# 20_WiFi_BT.net
KiCad netlist of a schematic drawn in Altium Designer
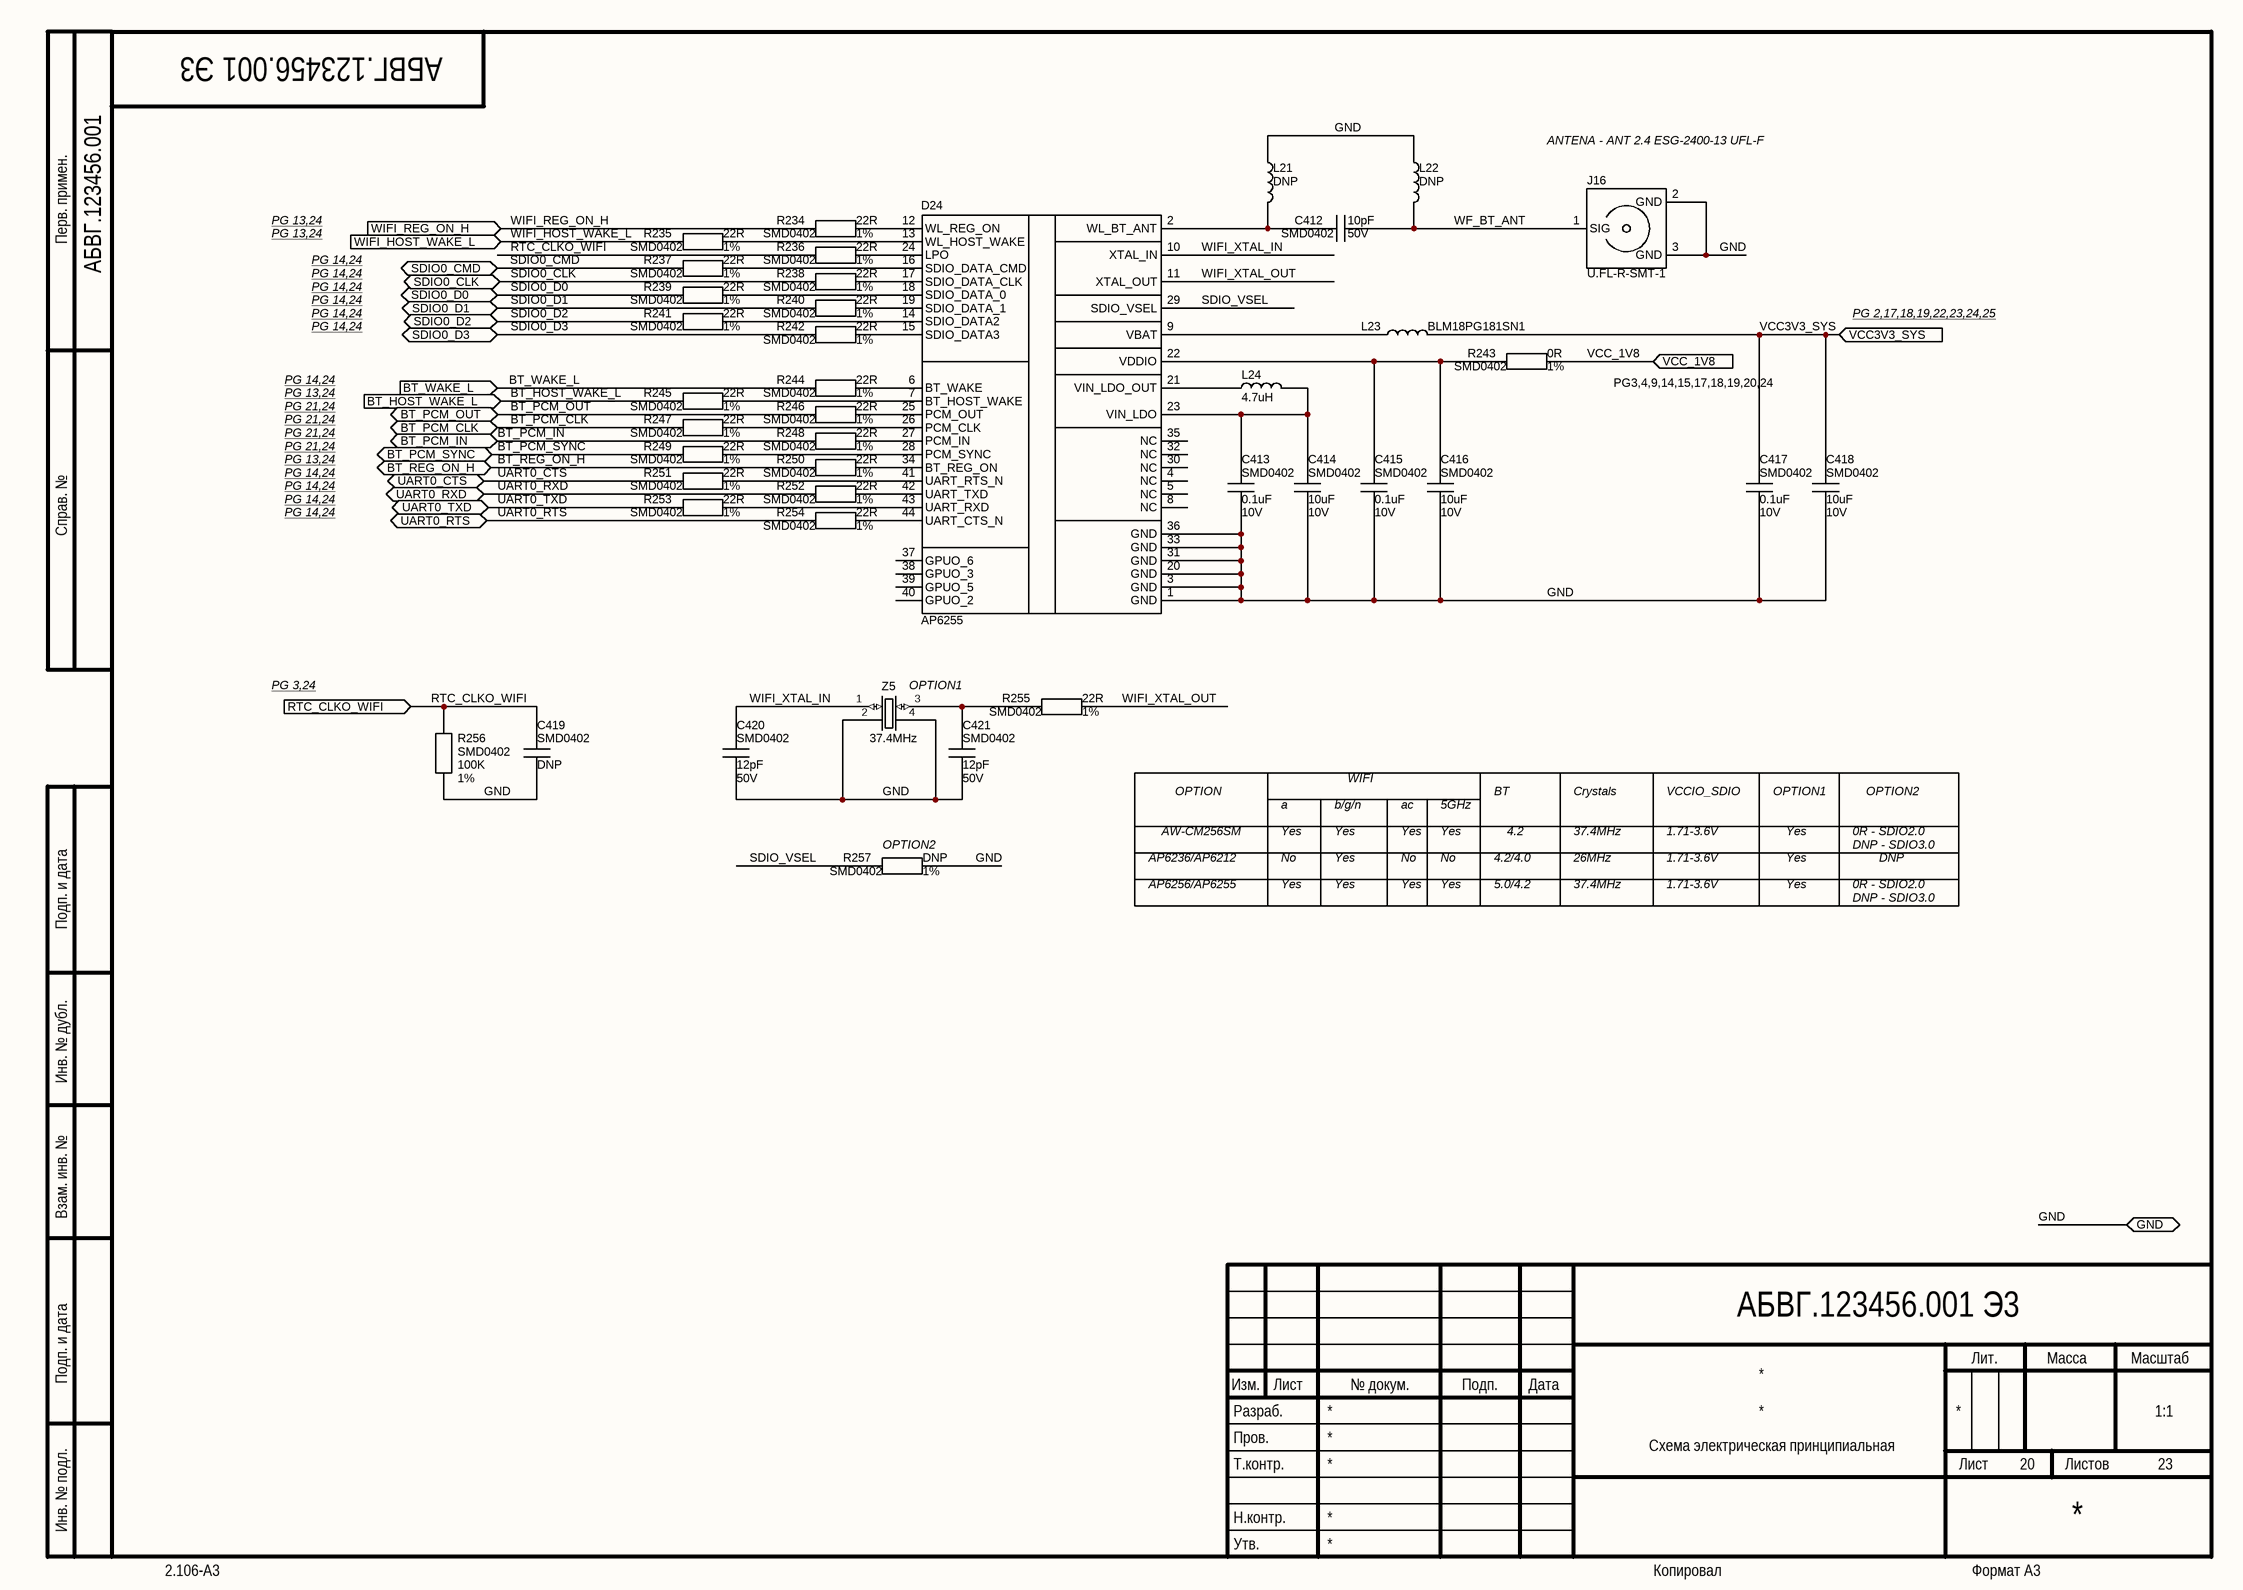
[diagram p0: 20 WiFi_BT.SchDoc]

(export (version "E")
  (design (tool "Eeschema 10.0.6"))
  (components
    (comp (ref "C412")
      (value "10pF")
      (footprint "Didur_PcbLib_1:CAP_SMD_0402")
      (fields
        (field (name "PACKAGE") "SMD0402")
        (field (name "PARTNUMBER") "CC0402CRNPO9BN100")
        (field (name "VOLTAGE") "50V")
      )
      (libsource (lib "Didur_SchLib_1") (part "Ceramic_Cap"))
    )
    (comp (ref "C413")
      (value "0.1uF")
      (footprint "Didur_PcbLib_1:CAP_SMD_0402")
      (fields
        (field (name "PACKAGE") "SMD0402")
        (field (name "PARTNUMBER") "CC0402KRX5R6BB104")
        (field (name "VOLTAGE") "10V")
      )
      (libsource (lib "Didur_SchLib_1") (part "Ceramic_Cap"))
    )
    (comp (ref "C414")
      (value "10uF")
      (footprint "Didur_PcbLib_1:CAP_SMD_0402")
      (fields
        (field (name "PACKAGE") "SMD0402")
        (field (name "PARTNUMBER") "CC0402MRX5R6BB106")
        (field (name "VOLTAGE") "10V")
      )
      (libsource (lib "Didur_SchLib_1") (part "Ceramic_Cap"))
    )
    (comp (ref "C415")
      (value "0.1uF")
      (footprint "Didur_PcbLib_1:CAP_SMD_0402")
      (fields
        (field (name "PACKAGE") "SMD0402")
        (field (name "PARTNUMBER") "CC0402KRX5R6BB104")
        (field (name "VOLTAGE") "10V")
      )
      (libsource (lib "Didur_SchLib_1") (part "Ceramic_Cap"))
    )
    (comp (ref "C416")
      (value "10uF")
      (footprint "Didur_PcbLib_1:CAP_SMD_0402")
      (fields
        (field (name "PACKAGE") "SMD0402")
        (field (name "PARTNUMBER") "CC0402MRX5R6BB106")
        (field (name "VOLTAGE") "10V")
      )
      (libsource (lib "Didur_SchLib_1") (part "Ceramic_Cap"))
    )
    (comp (ref "C417")
      (value "0.1uF")
      (footprint "Didur_PcbLib_1:CAP_SMD_0402")
      (fields
        (field (name "PACKAGE") "SMD0402")
        (field (name "PARTNUMBER") "CC0402KRX5R6BB104")
        (field (name "VOLTAGE") "10V")
      )
      (libsource (lib "Didur_SchLib_1") (part "Ceramic_Cap"))
    )
    (comp (ref "C418")
      (value "10uF")
      (footprint "Didur_PcbLib_1:CAP_SMD_0402")
      (fields
        (field (name "PACKAGE") "SMD0402")
        (field (name "PARTNUMBER") "CC0402MRX5R6BB106")
        (field (name "VOLTAGE") "10V")
      )
      (libsource (lib "Didur_SchLib_1") (part "Ceramic_Cap"))
    )
    (comp (ref "C419")
      (value "DNP")
      (footprint "Didur_PcbLib_1:CAP_SMD_0402")
      (fields (field (name "PACKAGE") "SMD0402") (field (name "PARTNUMBER") "Do Not Place"))
      (libsource (lib "Didur_SchLib_1") (part "Ceramic_Cap"))
    )
    (comp (ref "C420")
      (value "12pF")
      (footprint "Didur_PcbLib_1:CAP_SMD_0402")
      (fields
        (field (name "PACKAGE") "SMD0402")
        (field (name "PARTNUMBER") "CC0402JRNPO9BN120")
        (field (name "VOLTAGE") "50V")
      )
      (libsource (lib "Didur_SchLib_1") (part "Ceramic_Cap"))
    )
    (comp (ref "C421")
      (value "12pF")
      (footprint "Didur_PcbLib_1:CAP_SMD_0402")
      (fields
        (field (name "PACKAGE") "SMD0402")
        (field (name "PARTNUMBER") "CC0402JRNPO9BN120")
        (field (name "VOLTAGE") "50V")
      )
      (libsource (lib "Didur_SchLib_1") (part "Ceramic_Cap"))
    )
    (comp (ref "D24")
      (value "AP6255")
      (footprint "Didur_PcbLib_1:AP6255")
      (libsource (lib "Didur_SchLib_1") (part "AP6255"))
    )
    (comp (ref "J16")
      (value "U.FL-R-SMT-1")
      (footprint "Didur_PcbLib_1:U.FL-R-SMT-1")
      (libsource (lib "Didur_SchLib_1") (part "UFL_CON"))
    )
    (comp (ref "L21")
      (value "DNP")
      (footprint "Didur_PcbLib_1:IND_SMD_0402")
      (fields (field (name "PARTNUMBER") "Do Not Place") (field (name "Comment") "Value"))
      (libsource (lib "Didur_SchLib_1") (part "Inductor_smal"))
    )
    (comp (ref "L22")
      (value "DNP")
      (footprint "Didur_PcbLib_1:IND_SMD_0402")
      (fields (field (name "PARTNUMBER") "Do Not Place") (field (name "Comment") "Value"))
      (libsource (lib "Didur_SchLib_1") (part "Inductor_smal"))
    )
    (comp (ref "L23")
      (value "BLM18PG181SN1")
      (footprint "Didur_PcbLib_1:IND_SMD_0603")
      (fields (field (name "Comment") "Value"))
      (libsource (lib "Didur_SchLib_1") (part "Inductor_smal"))
    )
    (comp (ref "L24")
      (value "4.7uH")
      (footprint "Didur_PcbLib_1:MWSA0402S")
      (fields (field (name "PARTNUMBER") "MWSA0402S-4R7MT") (field (name "Comment") "Value"))
      (libsource (lib "Didur_SchLib_1") (part "Inductor_smal"))
    )
    (comp (ref "R234")
      (value "22R")
      (footprint "Didur_PcbLib_1:RES_SMD_0402")
      (fields
        (field (name "PACKAGE") "SMD0402")
        (field (name "PARTNUMBER") "RC0402FR-0722RL")
        (field (name "TOLERANCE") "1%")
      )
      (libsource (lib "Didur_SchLib_1") (part "Chip_Res"))
    )
    (comp (ref "R235")
      (value "22R")
      (footprint "Didur_PcbLib_1:RES_SMD_0402")
      (fields
        (field (name "PACKAGE") "SMD0402")
        (field (name "PARTNUMBER") "RC0402FR-0722RL")
        (field (name "TOLERANCE") "1%")
      )
      (libsource (lib "Didur_SchLib_1") (part "Chip_Res"))
    )
    (comp (ref "R236")
      (value "22R")
      (footprint "Didur_PcbLib_1:RES_SMD_0402")
      (fields
        (field (name "PACKAGE") "SMD0402")
        (field (name "PARTNUMBER") "RC0402FR-0722RL")
        (field (name "TOLERANCE") "1%")
      )
      (libsource (lib "Didur_SchLib_1") (part "Chip_Res"))
    )
    (comp (ref "R237")
      (value "22R")
      (footprint "Didur_PcbLib_1:RES_SMD_0402")
      (fields
        (field (name "PACKAGE") "SMD0402")
        (field (name "PARTNUMBER") "RC0402FR-0722RL")
        (field (name "TOLERANCE") "1%")
      )
      (libsource (lib "Didur_SchLib_1") (part "Chip_Res"))
    )
    (comp (ref "R238")
      (value "22R")
      (footprint "Didur_PcbLib_1:RES_SMD_0402")
      (fields
        (field (name "PACKAGE") "SMD0402")
        (field (name "PARTNUMBER") "RC0402FR-0722RL")
        (field (name "TOLERANCE") "1%")
      )
      (libsource (lib "Didur_SchLib_1") (part "Chip_Res"))
    )
    (comp (ref "R239")
      (value "22R")
      (footprint "Didur_PcbLib_1:RES_SMD_0402")
      (fields
        (field (name "PACKAGE") "SMD0402")
        (field (name "PARTNUMBER") "RC0402FR-0722RL")
        (field (name "TOLERANCE") "1%")
      )
      (libsource (lib "Didur_SchLib_1") (part "Chip_Res"))
    )
    (comp (ref "R240")
      (value "22R")
      (footprint "Didur_PcbLib_1:RES_SMD_0402")
      (fields
        (field (name "PACKAGE") "SMD0402")
        (field (name "PARTNUMBER") "RC0402FR-0722RL")
        (field (name "TOLERANCE") "1%")
      )
      (libsource (lib "Didur_SchLib_1") (part "Chip_Res"))
    )
    (comp (ref "R241")
      (value "22R")
      (footprint "Didur_PcbLib_1:RES_SMD_0402")
      (fields
        (field (name "PACKAGE") "SMD0402")
        (field (name "PARTNUMBER") "RC0402FR-0722RL")
        (field (name "TOLERANCE") "1%")
      )
      (libsource (lib "Didur_SchLib_1") (part "Chip_Res"))
    )
    (comp (ref "R242")
      (value "22R")
      (footprint "Didur_PcbLib_1:RES_SMD_0402")
      (fields
        (field (name "PACKAGE") "SMD0402")
        (field (name "PARTNUMBER") "RC0402FR-0722RL")
        (field (name "TOLERANCE") "1%")
      )
      (libsource (lib "Didur_SchLib_1") (part "Chip_Res"))
    )
    (comp (ref "R243")
      (value "0R")
      (footprint "Didur_PcbLib_1:RES_SMD_0402")
      (fields
        (field (name "PACKAGE") "SMD0402")
        (field (name "PARTNUMBER") "RC0402FR-070RL")
        (field (name "TOLERANCE") "1%")
      )
      (libsource (lib "") (part "Chip_Res_1"))
    )
    (comp (ref "R244")
      (value "22R")
      (footprint "Didur_PcbLib_1:RES_SMD_0402")
      (fields
        (field (name "PACKAGE") "SMD0402")
        (field (name "PARTNUMBER") "RC0402FR-0722RL")
        (field (name "TOLERANCE") "1%")
      )
      (libsource (lib "Didur_SchLib_1") (part "Chip_Res"))
    )
    (comp (ref "R245")
      (value "22R")
      (footprint "Didur_PcbLib_1:RES_SMD_0402")
      (fields
        (field (name "PACKAGE") "SMD0402")
        (field (name "PARTNUMBER") "RC0402FR-0722RL")
        (field (name "TOLERANCE") "1%")
      )
      (libsource (lib "Didur_SchLib_1") (part "Chip_Res"))
    )
    (comp (ref "R246")
      (value "22R")
      (footprint "Didur_PcbLib_1:RES_SMD_0402")
      (fields
        (field (name "PACKAGE") "SMD0402")
        (field (name "PARTNUMBER") "RC0402FR-0722RL")
        (field (name "TOLERANCE") "1%")
      )
      (libsource (lib "Didur_SchLib_1") (part "Chip_Res"))
    )
    (comp (ref "R247")
      (value "22R")
      (footprint "Didur_PcbLib_1:RES_SMD_0402")
      (fields
        (field (name "PACKAGE") "SMD0402")
        (field (name "PARTNUMBER") "RC0402FR-0722RL")
        (field (name "TOLERANCE") "1%")
      )
      (libsource (lib "Didur_SchLib_1") (part "Chip_Res"))
    )
    (comp (ref "R248")
      (value "22R")
      (footprint "Didur_PcbLib_1:RES_SMD_0402")
      (fields
        (field (name "PACKAGE") "SMD0402")
        (field (name "PARTNUMBER") "RC0402FR-0722RL")
        (field (name "TOLERANCE") "1%")
      )
      (libsource (lib "Didur_SchLib_1") (part "Chip_Res"))
    )
    (comp (ref "R249")
      (value "22R")
      (footprint "Didur_PcbLib_1:RES_SMD_0402")
      (fields
        (field (name "PACKAGE") "SMD0402")
        (field (name "PARTNUMBER") "RC0402FR-0722RL")
        (field (name "TOLERANCE") "1%")
      )
      (libsource (lib "Didur_SchLib_1") (part "Chip_Res"))
    )
    (comp (ref "R250")
      (value "22R")
      (footprint "Didur_PcbLib_1:RES_SMD_0402")
      (fields
        (field (name "PACKAGE") "SMD0402")
        (field (name "PARTNUMBER") "RC0402FR-0722RL")
        (field (name "TOLERANCE") "1%")
      )
      (libsource (lib "Didur_SchLib_1") (part "Chip_Res"))
    )
    (comp (ref "R251")
      (value "22R")
      (footprint "Didur_PcbLib_1:RES_SMD_0402")
      (fields
        (field (name "PACKAGE") "SMD0402")
        (field (name "PARTNUMBER") "RC0402FR-0722RL")
        (field (name "TOLERANCE") "1%")
      )
      (libsource (lib "Didur_SchLib_1") (part "Chip_Res"))
    )
    (comp (ref "R252")
      (value "22R")
      (footprint "Didur_PcbLib_1:RES_SMD_0402")
      (fields
        (field (name "PACKAGE") "SMD0402")
        (field (name "PARTNUMBER") "RC0402FR-0722RL")
        (field (name "TOLERANCE") "1%")
      )
      (libsource (lib "Didur_SchLib_1") (part "Chip_Res"))
    )
    (comp (ref "R253")
      (value "22R")
      (footprint "Didur_PcbLib_1:RES_SMD_0402")
      (fields
        (field (name "PACKAGE") "SMD0402")
        (field (name "PARTNUMBER") "RC0402FR-0722RL")
        (field (name "TOLERANCE") "1%")
      )
      (libsource (lib "Didur_SchLib_1") (part "Chip_Res"))
    )
    (comp (ref "R254")
      (value "22R")
      (footprint "Didur_PcbLib_1:RES_SMD_0402")
      (fields
        (field (name "PACKAGE") "SMD0402")
        (field (name "PARTNUMBER") "RC0402FR-0722RL")
        (field (name "TOLERANCE") "1%")
      )
      (libsource (lib "Didur_SchLib_1") (part "Chip_Res"))
    )
    (comp (ref "R255")
      (value "22R")
      (footprint "Didur_PcbLib_1:RES_SMD_0402")
      (fields
        (field (name "PACKAGE") "SMD0402")
        (field (name "PARTNUMBER") "RC0402FR-0722RL")
        (field (name "TOLERANCE") "1%")
      )
      (libsource (lib "Didur_SchLib_1") (part "Chip_Res"))
    )
    (comp (ref "R256")
      (value "100K")
      (footprint "Didur_PcbLib_1:RES_SMD_0402")
      (fields
        (field (name "PACKAGE") "SMD0402")
        (field (name "PARTNUMBER") "RC0402FR-07100KL")
        (field (name "TOLERANCE") "1%")
      )
      (libsource (lib "") (part "Chip_Res_1"))
    )
    (comp (ref "R257")
      (value "DNP")
      (footprint "Didur_PcbLib_1:RES_SMD_0402")
      (fields
        (field (name "PACKAGE") "SMD0402")
        (field (name "PARTNUMBER") "Do Not Place")
        (field (name "TOLERANCE") "1%")
      )
      (libsource (lib "Didur_SchLib_1") (part "Chip_Res"))
    )
    (comp (ref "Z5")
      (value "37.4MHz")
      (footprint "Didur_PcbLib_1:TSX3225")
      (fields (field (name "PARTNUMBER") "X3225374MOB4SI") (field (name "Comment") "Value"))
      (libsource (lib "Didur_SchLib_1") (part "OSC3225"))
    )
  )
  (nets
    (net (code "1") (name "/BT_HOST_WAKE_L") (class "Default")
      (node (ref "R245") (pin "1") (pinfunction "1_1") (pintype "passive"))
    )
    (net (code "2") (name "/BT_PCM_CLK") (class "Default")
      (node (ref "R247") (pin "1") (pinfunction "1_1") (pintype "passive"))
    )
    (net (code "3") (name "/BT_PCM_IN") (class "Default")
      (node (ref "R248") (pin "1") (pinfunction "1_1") (pintype "passive"))
    )
    (net (code "4") (name "/BT_PCM_OUT") (class "Default")
      (node (ref "R246") (pin "1") (pinfunction "1_1") (pintype "passive"))
    )
    (net (code "5") (name "/BT_PCM_SYNC") (class "Default")
      (node (ref "R249") (pin "1") (pinfunction "1_1") (pintype "passive"))
    )
    (net (code "6") (name "/BT_REG_ON_H") (class "Default")
      (node (ref "R250") (pin "1") (pinfunction "1_1") (pintype "passive"))
    )
    (net (code "7") (name "/BT_WAKE_L") (class "Default")
      (node (ref "R244") (pin "1") (pinfunction "1_1") (pintype "passive"))
    )
    (net (code "8") (name "/GND") (class "Default")
      (node (ref "C413") (pin "2") (pinfunction "2_2") (pintype "power_in"))
      (node (ref "C414") (pin "2") (pinfunction "2_2") (pintype "power_in"))
      (node (ref "C415") (pin "2") (pinfunction "2_2") (pintype "power_in"))
      (node (ref "C416") (pin "2") (pinfunction "2_2") (pintype "power_in"))
      (node (ref "C417") (pin "2") (pinfunction "2_2") (pintype "power_in"))
      (node (ref "C418") (pin "2") (pinfunction "2_2") (pintype "power_in"))
      (node (ref "C419") (pin "1") (pinfunction "1_1") (pintype "power_in"))
      (node (ref "C420") (pin "2") (pinfunction "2_2") (pintype "power_in"))
      (node (ref "C421") (pin "2") (pinfunction "2_2") (pintype "power_in"))
      (node (ref "D24") (pin "1") (pinfunction "GND_1") (pintype "passive"))
      (node (ref "D24") (pin "20") (pinfunction "GND_20") (pintype "passive"))
      (node (ref "D24") (pin "3") (pinfunction "GND_3") (pintype "passive"))
      (node (ref "D24") (pin "31") (pinfunction "GND_31") (pintype "passive"))
      (node (ref "D24") (pin "33") (pinfunction "GND_33") (pintype "passive"))
      (node (ref "D24") (pin "36") (pinfunction "GND_36") (pintype "passive"))
      (node (ref "J16") (pin "2") (pinfunction "GND_2") (pintype "passive"))
      (node (ref "J16") (pin "3") (pinfunction "GND_3") (pintype "passive"))
      (node (ref "L21") (pin "2") (pinfunction "2_2") (pintype "passive"))
      (node (ref "L22") (pin "2") (pinfunction "2_2") (pintype "passive"))
      (node (ref "R256") (pin "1") (pinfunction "1_1") (pintype "passive"))
      (node (ref "R257") (pin "2") (pinfunction "2_2") (pintype "passive"))
      (node (ref "Z5") (pin "2") (pinfunction "GND_2") (pintype "passive"))
      (node (ref "Z5") (pin "4") (pinfunction "GND_4") (pintype "passive"))
    )
    (net (code "9") (name "/RTC_CLKO_WIFI") (class "Default")
      (node (ref "C419") (pin "2") (pinfunction "2_2") (pintype "power_in"))
      (node (ref "R236") (pin "1") (pinfunction "1_1") (pintype "passive"))
      (node (ref "R256") (pin "2") (pinfunction "2_2") (pintype "passive"))
    )
    (net (code "10") (name "/SDIO0_CLK") (class "Default")
      (node (ref "R238") (pin "1") (pinfunction "1_1") (pintype "passive"))
    )
    (net (code "11") (name "/SDIO0_CMD") (class "Default")
      (node (ref "R237") (pin "1") (pinfunction "1_1") (pintype "passive"))
    )
    (net (code "12") (name "/SDIO0_D0") (class "Default")
      (node (ref "R239") (pin "1") (pinfunction "1_1") (pintype "passive"))
    )
    (net (code "13") (name "/SDIO0_D1") (class "Default")
      (node (ref "R240") (pin "1") (pinfunction "1_1") (pintype "passive"))
    )
    (net (code "14") (name "/SDIO0_D2") (class "Default")
      (node (ref "R241") (pin "1") (pinfunction "1_1") (pintype "passive"))
    )
    (net (code "15") (name "/SDIO0_D3") (class "Default")
      (node (ref "R242") (pin "1") (pinfunction "1_1") (pintype "passive"))
    )
    (net (code "16") (name "/SDIO_VSEL") (class "Default")
      (node (ref "D24") (pin "29") (pinfunction "SDIO_VSEL_29") (pintype "passive"))
      (node (ref "R257") (pin "1") (pinfunction "1_1") (pintype "passive"))
    )
    (net (code "17") (name "/UART0_CTS") (class "Default")
      (node (ref "R251") (pin "1") (pinfunction "1_1") (pintype "passive"))
    )
    (net (code "18") (name "/UART0_RTS") (class "Default")
      (node (ref "R254") (pin "1") (pinfunction "1_1") (pintype "passive"))
    )
    (net (code "19") (name "/UART0_RXD") (class "Default")
      (node (ref "R252") (pin "1") (pinfunction "1_1") (pintype "passive"))
    )
    (net (code "20") (name "/UART0_TXD") (class "Default")
      (node (ref "R253") (pin "1") (pinfunction "1_1") (pintype "passive"))
    )
    (net (code "21") (name "/VCC3V3_SYS") (class "Default")
      (node (ref "C417") (pin "1") (pinfunction "1_1") (pintype "power_in"))
      (node (ref "C418") (pin "1") (pinfunction "1_1") (pintype "power_in"))
      (node (ref "L23") (pin "1") (pinfunction "1_1") (pintype "passive"))
    )
    (net (code "22") (name "/VCC_1V8") (class "Default")
      (node (ref "R243") (pin "2") (pinfunction "2_2") (pintype "passive"))
    )
    (net (code "23") (name "/WF_BT_ANT") (class "Default")
      (node (ref "C412") (pin "2") (pinfunction "2_2") (pintype "power_in"))
      (node (ref "J16") (pin "1") (pinfunction "SIG_1") (pintype "passive"))
      (node (ref "L22") (pin "1") (pinfunction "1_1") (pintype "passive"))
    )
    (net (code "24") (name "/WIFI_HOST_WAKE_L") (class "Default")
      (node (ref "R235") (pin "1") (pinfunction "1_1") (pintype "passive"))
    )
    (net (code "25") (name "/WIFI_REG_ON_H") (class "Default")
      (node (ref "R234") (pin "1") (pinfunction "1_1") (pintype "passive"))
    )
    (net (code "26") (name "/WIFI_XTAL_IN") (class "Default")
      (node (ref "C420") (pin "1") (pinfunction "1_1") (pintype "power_in"))
      (node (ref "D24") (pin "10") (pinfunction "XTAL_IN_10") (pintype "passive"))
      (node (ref "Z5") (pin "1") (pinfunction "IN/OUT_1") (pintype "bidirectional"))
    )
    (net (code "27") (name "/WIFI_XTAL_OUT") (class "Default")
      (node (ref "D24") (pin "11") (pinfunction "XTAL_OUT_11") (pintype "passive"))
      (node (ref "R255") (pin "2") (pinfunction "2_2") (pintype "passive"))
    )
    (net (code "28") (name "Net-(C421-Pad1)") (class "Default")
      (node (ref "C421") (pin "1") (pinfunction "1_1") (pintype "power_in"))
      (node (ref "R255") (pin "1") (pinfunction "1_1") (pintype "passive"))
      (node (ref "Z5") (pin "3") (pinfunction "IN/OUT_3") (pintype "bidirectional"))
    )
    (net (code "29") (name "Net-(D24-BT_HOST_WAKE)") (class "Default")
      (node (ref "D24") (pin "7") (pinfunction "BT_HOST_WAKE_7") (pintype "passive"))
      (node (ref "R245") (pin "2") (pinfunction "2_2") (pintype "passive"))
    )
    (net (code "30") (name "Net-(D24-BT_REG_ON)") (class "Default")
      (node (ref "D24") (pin "34") (pinfunction "BT_REG_ON_34") (pintype "passive"))
      (node (ref "R250") (pin "2") (pinfunction "2_2") (pintype "passive"))
    )
    (net (code "31") (name "Net-(D24-BT_WAKE)") (class "Default")
      (node (ref "D24") (pin "6") (pinfunction "BT_WAKE_6") (pintype "passive"))
      (node (ref "R244") (pin "2") (pinfunction "2_2") (pintype "passive"))
    )
    (net (code "32") (name "Net-(D24-LPO)") (class "Default")
      (node (ref "D24") (pin "24") (pinfunction "LPO_24") (pintype "passive"))
      (node (ref "R236") (pin "2") (pinfunction "2_2") (pintype "passive"))
    )
    (net (code "33") (name "Net-(D24-PCM_CLK)") (class "Default")
      (node (ref "D24") (pin "26") (pinfunction "PCM_CLK_26") (pintype "passive"))
      (node (ref "R247") (pin "2") (pinfunction "2_2") (pintype "passive"))
    )
    (net (code "34") (name "Net-(D24-PCM_IN)") (class "Default")
      (node (ref "D24") (pin "27") (pinfunction "PCM_IN_27") (pintype "passive"))
      (node (ref "R248") (pin "2") (pinfunction "2_2") (pintype "passive"))
    )
    (net (code "35") (name "Net-(D24-PCM_OUT)") (class "Default")
      (node (ref "D24") (pin "25") (pinfunction "PCM_OUT_25") (pintype "passive"))
      (node (ref "R246") (pin "2") (pinfunction "2_2") (pintype "passive"))
    )
    (net (code "36") (name "Net-(D24-PCM_SYNC)") (class "Default")
      (node (ref "D24") (pin "28") (pinfunction "PCM_SYNC_28") (pintype "passive"))
      (node (ref "R249") (pin "2") (pinfunction "2_2") (pintype "passive"))
    )
    (net (code "37") (name "Net-(D24-SDIO_DATA2)") (class "Default")
      (node (ref "D24") (pin "14") (pinfunction "SDIO_DATA2_14") (pintype "passive"))
      (node (ref "R241") (pin "2") (pinfunction "2_2") (pintype "passive"))
    )
    (net (code "38") (name "Net-(D24-SDIO_DATA3)") (class "Default")
      (node (ref "D24") (pin "15") (pinfunction "SDIO_DATA3_15") (pintype "passive"))
      (node (ref "R242") (pin "2") (pinfunction "2_2") (pintype "passive"))
    )
    (net (code "39") (name "Net-(D24-SDIO_DATA_0)") (class "Default")
      (node (ref "D24") (pin "18") (pinfunction "SDIO_DATA_0_18") (pintype "passive"))
      (node (ref "R239") (pin "2") (pinfunction "2_2") (pintype "passive"))
    )
    (net (code "40") (name "Net-(D24-SDIO_DATA_1)") (class "Default")
      (node (ref "D24") (pin "19") (pinfunction "SDIO_DATA_1_19") (pintype "passive"))
      (node (ref "R240") (pin "2") (pinfunction "2_2") (pintype "passive"))
    )
    (net (code "41") (name "Net-(D24-SDIO_DATA_CLK)") (class "Default")
      (node (ref "D24") (pin "17") (pinfunction "SDIO_DATA_CLK_17") (pintype "passive"))
      (node (ref "R238") (pin "2") (pinfunction "2_2") (pintype "passive"))
    )
    (net (code "42") (name "Net-(D24-SDIO_DATA_CMD)") (class "Default")
      (node (ref "D24") (pin "16") (pinfunction "SDIO_DATA_CMD_16") (pintype "passive"))
      (node (ref "R237") (pin "2") (pinfunction "2_2") (pintype "passive"))
    )
    (net (code "43") (name "Net-(D24-UART_CTS_N)") (class "Default")
      (node (ref "D24") (pin "44") (pinfunction "UART_CTS_N_44") (pintype "passive"))
      (node (ref "R254") (pin "2") (pinfunction "2_2") (pintype "passive"))
    )
    (net (code "44") (name "Net-(D24-UART_RTS_N)") (class "Default")
      (node (ref "D24") (pin "41") (pinfunction "UART_RTS_N_41") (pintype "passive"))
      (node (ref "R251") (pin "2") (pinfunction "2_2") (pintype "passive"))
    )
    (net (code "45") (name "Net-(D24-UART_RXD)") (class "Default")
      (node (ref "D24") (pin "43") (pinfunction "UART_RXD_43") (pintype "passive"))
      (node (ref "R253") (pin "2") (pinfunction "2_2") (pintype "passive"))
    )
    (net (code "46") (name "Net-(D24-UART_TXD)") (class "Default")
      (node (ref "D24") (pin "42") (pinfunction "UART_TXD_42") (pintype "passive"))
      (node (ref "R252") (pin "2") (pinfunction "2_2") (pintype "passive"))
    )
    (net (code "47") (name "Net-(D24-VBAT)") (class "Default")
      (node (ref "D24") (pin "9") (pinfunction "VBAT_9") (pintype "passive"))
      (node (ref "L23") (pin "2") (pinfunction "2_2") (pintype "passive"))
    )
    (net (code "48") (name "Net-(D24-VDDIO)") (class "Default")
      (node (ref "C415") (pin "1") (pinfunction "1_1") (pintype "power_in"))
      (node (ref "C416") (pin "1") (pinfunction "1_1") (pintype "power_in"))
      (node (ref "D24") (pin "22") (pinfunction "VDDIO_22") (pintype "passive"))
      (node (ref "R243") (pin "1") (pinfunction "1_1") (pintype "passive"))
    )
    (net (code "49") (name "Net-(D24-VIN_LDO)") (class "Default")
      (node (ref "C413") (pin "1") (pinfunction "1_1") (pintype "power_in"))
      (node (ref "C414") (pin "1") (pinfunction "1_1") (pintype "power_in"))
      (node (ref "D24") (pin "23") (pinfunction "VIN_LDO_23") (pintype "passive"))
      (node (ref "L24") (pin "1") (pinfunction "1_1") (pintype "passive"))
    )
    (net (code "50") (name "Net-(D24-VIN_LDO_OUT)") (class "Default")
      (node (ref "D24") (pin "21") (pinfunction "VIN_LDO_OUT_21") (pintype "passive"))
      (node (ref "L24") (pin "2") (pinfunction "2_2") (pintype "passive"))
    )
    (net (code "51") (name "Net-(D24-WL_BT_ANT)") (class "Default")
      (node (ref "C412") (pin "1") (pinfunction "1_1") (pintype "power_in"))
      (node (ref "D24") (pin "2") (pinfunction "WL_BT_ANT_2") (pintype "passive"))
      (node (ref "L21") (pin "1") (pinfunction "1_1") (pintype "passive"))
    )
    (net (code "52") (name "Net-(D24-WL_HOST_WAKE)") (class "Default")
      (node (ref "D24") (pin "13") (pinfunction "WL_HOST_WAKE_13") (pintype "passive"))
      (node (ref "R235") (pin "2") (pinfunction "2_2") (pintype "passive"))
    )
    (net (code "53") (name "Net-(D24-WL_REG_ON)") (class "Default")
      (node (ref "D24") (pin "12") (pinfunction "WL_REG_ON_12") (pintype "passive"))
      (node (ref "R234") (pin "2") (pinfunction "2_2") (pintype "passive"))
    )
    (net (code "54") (name "unconnected-(D24-GPUO_2-Pad40)") (class "Default")
      (node (ref "D24") (pin "40") (pinfunction "GPUO_2_40") (pintype "passive"))
    )
    (net (code "55") (name "unconnected-(D24-GPUO_3-Pad38)") (class "Default")
      (node (ref "D24") (pin "38") (pinfunction "GPUO_3_38") (pintype "passive"))
    )
    (net (code "56") (name "unconnected-(D24-GPUO_5-Pad39)") (class "Default")
      (node (ref "D24") (pin "39") (pinfunction "GPUO_5_39") (pintype "passive"))
    )
    (net (code "57") (name "unconnected-(D24-GPUO_6-Pad37)") (class "Default")
      (node (ref "D24") (pin "37") (pinfunction "GPUO_6_37") (pintype "passive"))
    )
    (net (code "58") (name "unconnected-(D24-NC-Pad4)") (class "Default")
      (node (ref "D24") (pin "4") (pinfunction "NC_4") (pintype "passive"))
    )
    (net (code "59") (name "unconnected-(D24-NC-Pad5)") (class "Default")
      (node (ref "D24") (pin "5") (pinfunction "NC_5") (pintype "passive"))
    )
    (net (code "60") (name "unconnected-(D24-NC-Pad8)") (class "Default")
      (node (ref "D24") (pin "8") (pinfunction "NC_8") (pintype "passive"))
    )
    (net (code "61") (name "unconnected-(D24-NC-Pad30)") (class "Default")
      (node (ref "D24") (pin "30") (pinfunction "NC_30") (pintype "passive"))
    )
    (net (code "62") (name "unconnected-(D24-NC-Pad32)") (class "Default")
      (node (ref "D24") (pin "32") (pinfunction "NC_32") (pintype "passive"))
    )
    (net (code "63") (name "unconnected-(D24-NC-Pad35)") (class "Default")
      (node (ref "D24") (pin "35") (pinfunction "NC_35") (pintype "passive"))
    )
  )
)
